# op.net
KiCad netlist of a schematic drawn in Altium Designer
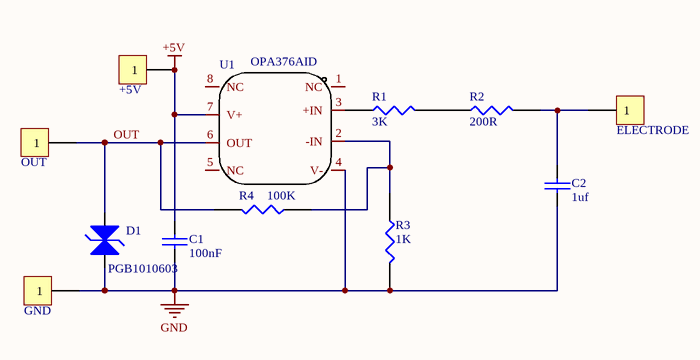
[diagram p0: op.SchDoc]

(export (version "E")
  (design (tool "Eeschema 10.0.6"))
  (components
    (comp (ref "+5V")
      (value "OUT")
      (footprint "P")
      (description "Connector")
      (libsource (lib "") (part "CON1_1"))
    )
    (comp (ref "C1")
      (value "100nF")
      (footprint "0603")
      (description "Capacitor")
      (libsource (lib "*") (part "CAP"))
    )
    (comp (ref "C2")
      (value "1uf")
      (footprint "0603")
      (description "Capacitor")
      (libsource (lib "*") (part "CAP"))
    )
    (comp (ref "D1") (value "PGB1010603") (footprint "0603") (libsource (lib "op") (part "DIODE")))
    (comp (ref "ELECTRODE")
      (value "ELECTRODE")
      (footprint "T")
      (description "Connector")
      (libsource (lib "*") (part "CON1"))
    )
    (comp (ref "GND")
      (value "GND")
      (footprint "P")
      (description "Connector")
      (libsource (lib "") (part "CON1_1"))
    )
    (comp (ref "OUT")
      (value "OUT")
      (footprint "P")
      (description "Connector")
      (libsource (lib "") (part "CON1_1"))
    )
    (comp (ref "R1") (value "3K") (footprint "0603") (libsource (lib "*") (part "RES1")))
    (comp (ref "R2") (value "200R") (footprint "0603") (libsource (lib "*") (part "RES1")))
    (comp (ref "R3") (value "1K") (footprint "0603") (libsource (lib "*") (part "RES1")))
    (comp (ref "R4") (value "100K") (footprint "0603") (libsource (lib "*") (part "RES1")))
    (comp (ref "U1") (value "OPA376AID") (footprint "SOIC-8") (libsource (lib "op") (part "376")))
  )
  (nets
    (net (code "1") (name "+5V") (class "Default")
      (node (ref "+5V") (pin "1") (pinfunction "1_1") (pintype "passive"))
      (node (ref "C1") (pin "1") (pinfunction "1_1") (pintype "passive"))
      (node (ref "U1") (pin "7") (pinfunction "V+_7") (pintype "passive"))
    )
    (net (code "2") (name "/OUT") (class "Default")
      (node (ref "D1") (pin "1") (pinfunction "1_1") (pintype "passive"))
      (node (ref "OUT") (pin "1") (pinfunction "1_1") (pintype "passive"))
      (node (ref "R4") (pin "2") (pinfunction "2_2") (pintype "passive"))
      (node (ref "U1") (pin "6") (pinfunction "OUT_6") (pintype "passive"))
    )
    (net (code "3") (name "GND") (class "Default")
      (node (ref "C1") (pin "2") (pinfunction "2_2") (pintype "passive"))
      (node (ref "C2") (pin "2") (pinfunction "2_2") (pintype "passive"))
      (node (ref "D1") (pin "2") (pinfunction "2_2") (pintype "passive"))
      (node (ref "GND") (pin "1") (pinfunction "1_1") (pintype "passive"))
      (node (ref "R3") (pin "2") (pinfunction "2_2") (pintype "passive"))
      (node (ref "U1") (pin "4") (pinfunction "V-_4") (pintype "passive"))
    )
    (net (code "4") (name "Net-(C2-Pad1)") (class "Default")
      (node (ref "C2") (pin "1") (pinfunction "1_1") (pintype "passive"))
      (node (ref "ELECTRODE") (pin "1") (pinfunction "1_1") (pintype "passive"))
      (node (ref "R2") (pin "2") (pinfunction "2_2") (pintype "passive"))
    )
    (net (code "5") (name "Net-(R1-Pad2)") (class "Default")
      (node (ref "R1") (pin "2") (pinfunction "2_2") (pintype "passive"))
      (node (ref "R2") (pin "1") (pinfunction "1_1") (pintype "passive"))
    )
    (net (code "6") (name "Net-(U1-+IN)") (class "Default")
      (node (ref "R1") (pin "1") (pinfunction "1_1") (pintype "passive"))
      (node (ref "U1") (pin "3") (pinfunction "+IN_3") (pintype "passive"))
    )
    (net (code "7") (name "Net-(U1--IN)") (class "Default")
      (node (ref "R3") (pin "1") (pinfunction "1_1") (pintype "passive"))
      (node (ref "R4") (pin "1") (pinfunction "1_1") (pintype "passive"))
      (node (ref "U1") (pin "2") (pinfunction "-IN_2") (pintype "passive"))
    )
    (net (code "8") (name "unconnected-(U1-NC-Pad1)") (class "Default")
      (node (ref "U1") (pin "1") (pinfunction "NC_1") (pintype "passive"))
    )
    (net (code "9") (name "unconnected-(U1-NC-Pad5)") (class "Default")
      (node (ref "U1") (pin "5") (pinfunction "NC_5") (pintype "passive"))
    )
    (net (code "10") (name "unconnected-(U1-NC-Pad8)") (class "Default")
      (node (ref "U1") (pin "8") (pinfunction "NC_8") (pintype "passive"))
    )
  )
)
